# 07_POWER-RAILS.net
KiCad netlist of a schematic drawn in Altium Designer
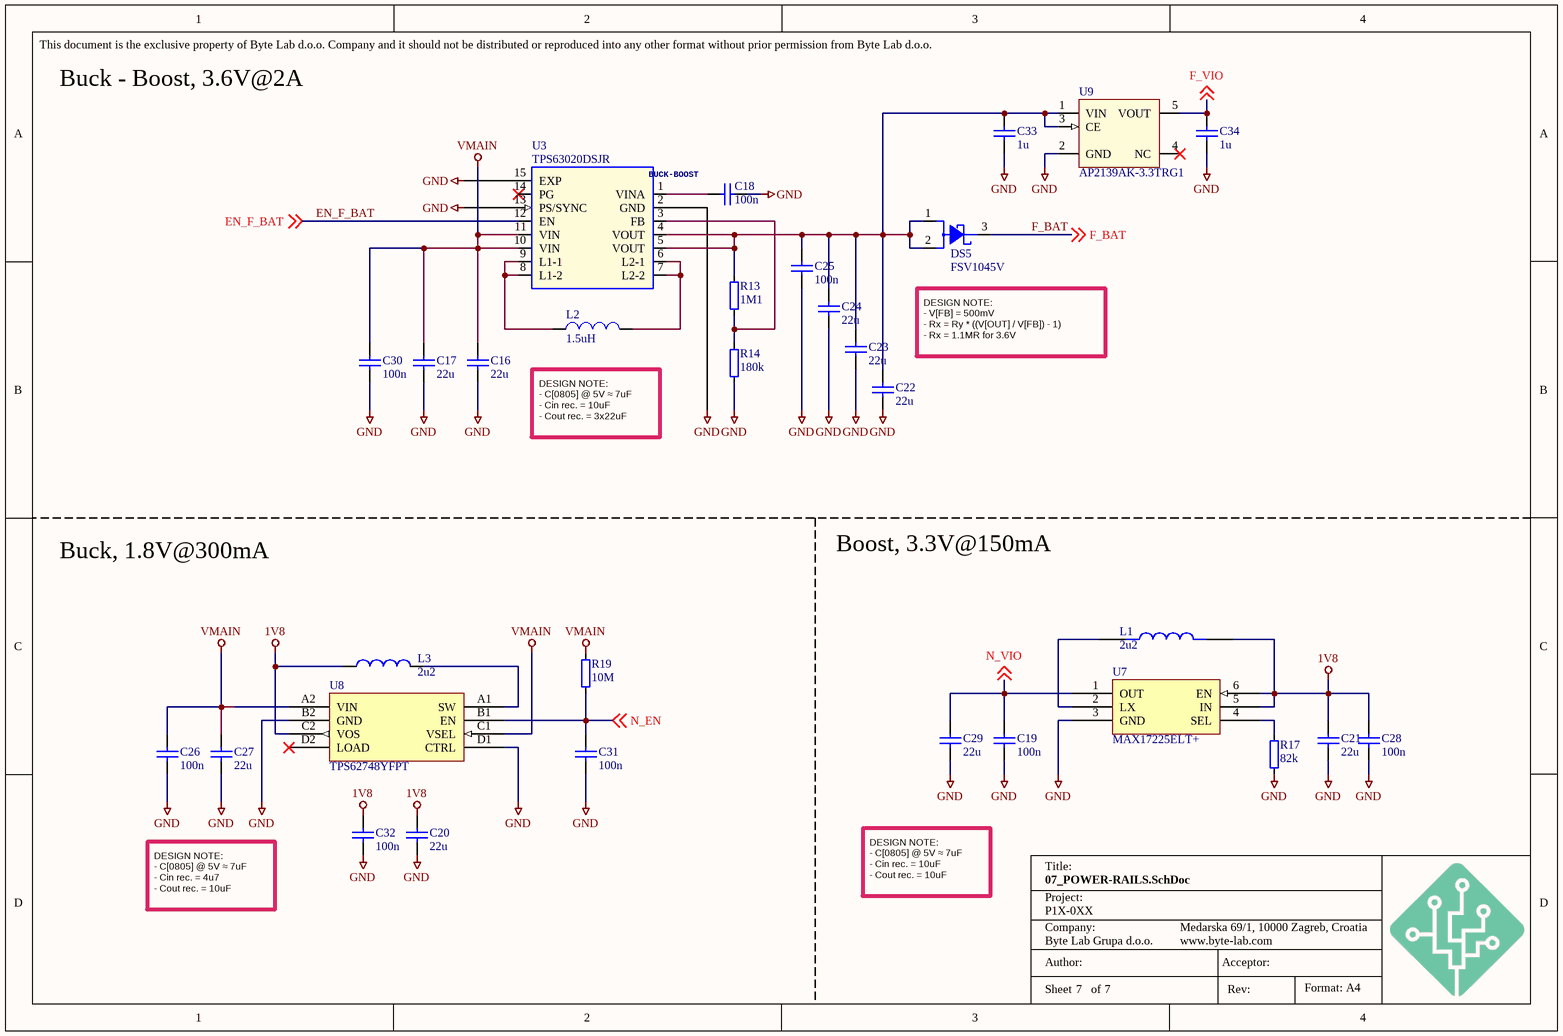
[diagram p0: 07_POWER-RAILS.SchDoc]

(export (version "E")
  (design (tool "Eeschema 10.0.6"))
  (components
    (comp (ref "C16")
      (value "22u")
      (footprint "C-0805")
      (description "Capacitor ceramic 22u ±10% X5R 16V 0805")
      (fields
        (field (name "BL PART NUMBER") "2006-222")
        (field (name "DRAWN_BY") "Fumic")
        (field (name "CHECKED_BY") "Hamin")
      )
      (libsource (lib "BL_Passive") (part "C0805-22u-16V-X5R"))
    )
    (comp (ref "C17")
      (value "22u")
      (footprint "C-0805")
      (description "Capacitor ceramic 22u ±10% X5R 16V 0805")
      (fields
        (field (name "BL PART NUMBER") "2006-222")
        (field (name "DRAWN_BY") "Fumic")
        (field (name "CHECKED_BY") "Hamin")
      )
      (libsource (lib "BL_Passive") (part "C0805-22u-16V-X5R"))
    )
    (comp (ref "C18")
      (value "100n")
      (footprint "C-0402")
      (description "Capacitor ceramic 100n ±10% X7R 16V 0402")
      (fields
        (field (name "BL PART NUMBER") "2000-908")
        (field (name "DRAWN_BY") "Puskar")
        (field (name "CHECKED_BY") "Dodig")
      )
      (libsource (lib "BL_Passive") (part "C0402-100n-16V-X7R"))
    )
    (comp (ref "C19")
      (value "100n")
      (footprint "C-0402")
      (description "Capacitor ceramic 100n ±10% X7R 16V 0402")
      (fields
        (field (name "BL PART NUMBER") "2000-908")
        (field (name "DRAWN_BY") "Puskar")
        (field (name "CHECKED_BY") "Dodig")
      )
      (libsource (lib "BL_Passive") (part "C0402-100n-16V-X7R"))
    )
    (comp (ref "C20")
      (value "22u")
      (footprint "C-0805")
      (description "Capacitor ceramic 22u ±10% X5R 16V 0805")
      (fields
        (field (name "BL PART NUMBER") "2006-222")
        (field (name "DRAWN_BY") "Fumic")
        (field (name "CHECKED_BY") "Hamin")
      )
      (libsource (lib "BL_Passive") (part "C0805-22u-16V-X5R"))
    )
    (comp (ref "C21")
      (value "22u")
      (footprint "C-0805")
      (description "Capacitor ceramic 22u ±10% X5R 16V 0805")
      (fields
        (field (name "BL PART NUMBER") "2006-222")
        (field (name "DRAWN_BY") "Fumic")
        (field (name "CHECKED_BY") "Hamin")
      )
      (libsource (lib "BL_Passive") (part "C0805-22u-16V-X5R"))
    )
    (comp (ref "C22")
      (value "22u")
      (footprint "C-0805")
      (description "Capacitor ceramic 22u ±10% X5R 16V 0805")
      (fields
        (field (name "BL PART NUMBER") "2006-222")
        (field (name "DRAWN_BY") "Fumic")
        (field (name "CHECKED_BY") "Hamin")
      )
      (libsource (lib "BL_Passive") (part "C0805-22u-16V-X5R"))
    )
    (comp (ref "C23")
      (value "22u")
      (footprint "C-0805")
      (description "Capacitor ceramic 22u ±10% X5R 16V 0805")
      (fields
        (field (name "BL PART NUMBER") "2006-222")
        (field (name "DRAWN_BY") "Fumic")
        (field (name "CHECKED_BY") "Hamin")
      )
      (libsource (lib "BL_Passive") (part "C0805-22u-16V-X5R"))
    )
    (comp (ref "C24")
      (value "22u")
      (footprint "C-0805")
      (description "Capacitor ceramic 22u ±10% X5R 16V 0805")
      (fields
        (field (name "BL PART NUMBER") "2006-222")
        (field (name "DRAWN_BY") "Fumic")
        (field (name "CHECKED_BY") "Hamin")
      )
      (libsource (lib "BL_Passive") (part "C0805-22u-16V-X5R"))
    )
    (comp (ref "C25")
      (value "100n")
      (footprint "C-0402")
      (description "Capacitor ceramic 100n ±10% X7R 16V 0402")
      (fields
        (field (name "BL PART NUMBER") "2000-908")
        (field (name "DRAWN_BY") "Puskar")
        (field (name "CHECKED_BY") "Dodig")
      )
      (libsource (lib "BL_Passive") (part "C0402-100n-16V-X7R"))
    )
    (comp (ref "C26")
      (value "100n")
      (footprint "C-0402")
      (description "Capacitor ceramic 100n ±10% X7R 16V 0402")
      (fields
        (field (name "BL PART NUMBER") "2000-908")
        (field (name "DRAWN_BY") "Puskar")
        (field (name "CHECKED_BY") "Dodig")
      )
      (libsource (lib "BL_Passive") (part "C0402-100n-16V-X7R"))
    )
    (comp (ref "C27")
      (value "22u")
      (footprint "C-0805")
      (description "Capacitor ceramic 22u ±10% X5R 16V 0805")
      (fields
        (field (name "BL PART NUMBER") "2006-222")
        (field (name "DRAWN_BY") "Fumic")
        (field (name "CHECKED_BY") "Hamin")
      )
      (libsource (lib "BL_Passive") (part "C0805-22u-16V-X5R"))
    )
    (comp (ref "C28")
      (value "100n")
      (footprint "C-0402")
      (description "Capacitor ceramic 100n ±10% X7R 16V 0402")
      (fields
        (field (name "BL PART NUMBER") "2000-908")
        (field (name "DRAWN_BY") "Puskar")
        (field (name "CHECKED_BY") "Dodig")
      )
      (libsource (lib "BL_Passive") (part "C0402-100n-16V-X7R"))
    )
    (comp (ref "C29")
      (value "22u")
      (footprint "C-0805")
      (description "Capacitor ceramic 22u ±10% X5R 16V 0805")
      (fields
        (field (name "BL PART NUMBER") "2006-222")
        (field (name "DRAWN_BY") "Fumic")
        (field (name "CHECKED_BY") "Hamin")
      )
      (libsource (lib "BL_Passive") (part "C0805-22u-16V-X5R"))
    )
    (comp (ref "C30")
      (value "100n")
      (footprint "C-0402")
      (description "Capacitor ceramic 100n ±10% X7R 16V 0402")
      (fields
        (field (name "BL PART NUMBER") "2000-908")
        (field (name "DRAWN_BY") "Puskar")
        (field (name "CHECKED_BY") "Dodig")
      )
      (libsource (lib "BL_Passive") (part "C0402-100n-16V-X7R"))
    )
    (comp (ref "C31")
      (value "100n")
      (footprint "C-0402")
      (description "Capacitor ceramic 100n ±10% X7R 16V 0402")
      (fields
        (field (name "BL PART NUMBER") "2000-908")
        (field (name "DRAWN_BY") "Puskar")
        (field (name "CHECKED_BY") "Dodig")
      )
      (libsource (lib "BL_Passive") (part "C0402-100n-16V-X7R"))
    )
    (comp (ref "C32")
      (value "100n")
      (footprint "C-0402")
      (description "Capacitor ceramic 100n ±10% X7R 16V 0402")
      (fields
        (field (name "BL PART NUMBER") "2000-908")
        (field (name "DRAWN_BY") "Puskar")
        (field (name "CHECKED_BY") "Dodig")
      )
      (libsource (lib "BL_Passive") (part "C0402-100n-16V-X7R"))
    )
    (comp (ref "C33")
      (value "1u")
      (footprint "C-0603")
      (description "Capacitor ceramic 1u ±10% X5R 25V")
      (fields
        (field (name "MANUFACTURER") "Yageo")
        (field (name "BL PART NUMBER") "2006-223")
        (field (name "DRAWN_BY") "Hamin")
        (field (name "CHECKED_BY") "Golubic")
      )
      (libsource (lib "BL_Passive") (part "C0603-1u-25V-X5R"))
    )
    (comp (ref "C34")
      (value "1u")
      (footprint "C-0603")
      (description "Capacitor ceramic 1u ±10% X5R 25V")
      (fields
        (field (name "MANUFACTURER") "Yageo")
        (field (name "BL PART NUMBER") "2006-223")
        (field (name "DRAWN_BY") "Hamin")
        (field (name "CHECKED_BY") "Golubic")
      )
      (libsource (lib "BL_Passive") (part "C0603-1u-25V-X5R"))
    )
    (comp (ref "DS5")
      (value "FSV1045V")
      (footprint "TO277-3")
      (description "DIODO SCHOTTKY 10A 45V FSV1045V TO277-3 SMT")
      (fields
        (field (name "BL PART NUMBER") "2007-712")
        (field (name "MANUFACTURER") "onsemi")
        (field (name "DRAWN_BY") "Blues Wireless")
      )
      (libsource (lib "n21-p2") (part "SCHOTTKY - FSV1045V - 10A/45V"))
    )
    (comp (ref "L1")
      (value "2u2")
      (footprint "IND_XFL4020-222MEC")
      (description "Power Inductors - SMD 2.2Uh Shld 8A 23.5mOhms AECQ2")
      (fields (field (name "BL PART NUMBER") "2007-483") (field (name "DRAWN_BY") "Blues Wireless"))
      (libsource (lib "n21-p2") (part "XFL4020-222MEC"))
    )
    (comp (ref "L2")
      (value "1.5uH")
      (footprint "VCHA042A-1R5MS6")
      (description "Fixed Ind 1.5UH 7.3A 15.4 Mohm")
      (fields
        (field (name "MANUFACTURER") "Cyntec")
        (field (name "MANUFACTURER PART NUMBER") "VCHA042A-1R5MS6")
        (field (name "DRAWN_BY") "Blues Wireless")
      )
      (libsource (lib "n21-p2") (part "VCHA042A-1R5MS6"))
    )
    (comp (ref "L3")
      (value "2u2")
      (footprint "1285AS-H-2R2M=P2-INDC2016X100N")
      (description "FIXED IND 2.2UH 1.5A 204MOHM SMD")
      (fields
        (field (name "MANUFACTURER") "Murata Electronics")
        (field (name "MANUFACTURER PART NUMBER") "1285AS-H-2R2M=P2")
        (field (name "DRAWN_BY") "Blues Wireless")
      )
      (libsource (lib "n21-p2") (part "1285AS-H-2R2M=P2"))
    )
    (comp (ref "R13")
      (value "1M1")
      (footprint "R-0402")
      (description "Resistor 1M1 ±1% 0402")
      (fields
        (field (name "BL PART NUMBER") "2000-730")
        (field (name "CHECKED_BY") "*")
        (field (name "DRAWN_BY") "Hamin")
      )
      (libsource (lib "BL_Passive") (part "R0402-1M1-1"))
    )
    (comp (ref "R14")
      (value "180k")
      (footprint "R-0402")
      (description "Resistor 180k ±1% 0402")
      (fields
        (field (name "BL PART NUMBER") "2001-422")
        (field (name "CHECKED_BY") "Hamin")
        (field (name "DRAWN_BY") "Dodig")
      )
      (libsource (lib "BL_Passive") (part "R0402-180k-1"))
    )
    (comp (ref "R17")
      (value "82k")
      (footprint "R-0402")
      (description "Resistor 82k ±1% 0402")
      (fields
        (field (name "MANUFACTURER") "Yageo")
        (field (name "MANUFACTURER PART NUMBER") "RC0402FR-0782KL")
        (field (name "CHECKED_BY") "Hamin")
        (field (name "DRAWN_BY") "Puskar")
      )
      (libsource (lib "BL_Passive") (part "R0402-82k-1"))
    )
    (comp (ref "R19")
      (value "10M")
      (footprint "BL_Passive:R-0402")
      (description "Resistor 10M ±1% 0402")
      (fields
        (field (name "BL PART NUMBER") "2002-832")
        (field (name "CHECKED_BY") "Dodig")
        (field (name "DRAWN_BY") "Zvonc")
      )
      (libsource (lib "BL_Passive") (part "R0402-10M-1"))
    )
    (comp (ref "U3")
      (value "TPS63020DSJR")
      (footprint "TI PVSON-14 DSJ")
      (description "I.C. DC/DC CONVERTER TPS63020DSJR TEXAS VSON14 SMT")
      (fields
        (field (name "BL PART NUMBER") "2002-405")
        (field (name "MANUFACTURER") "Texas Instruments")
        (field (name "DRAWN_BY") "Blues Wireless")
      )
      (libsource (lib "n21-p2") (part "BUCK-BOOST - TPS63020DSJR"))
    )
    (comp (ref "U7")
      (value "MAX17225ELT+")
      (footprint "MAX17225ELT+UDFN")
      (description "IC REG BOOST ADJ 1A NANO 6UDFN")
      (fields
        (field (name "MANUFACTURER") "Maxim")
        (field (name "BL PART NUMBER") "2007-481")
        (field (name "DRAWN_BY") "Blues Wireless")
      )
      (libsource (lib "n21-p2") (part "MAX17225ELT+"))
    )
    (comp (ref "U8")
      (value "TPS62748YFPT")
      (footprint "TPS62748YFPT-DSBGA4x2")
      (description "IC REG BUCK PROG 300MA 8DSBGA")
      (fields
        (field (name "MANUFACTURER") "Texas Instruments")
        (field (name "BL PART NUMBER") "2007-480")
        (field (name "DRAWN_BY") "Blues Wireless")
      )
      (libsource (lib "n21-p2") (part "TPS62748YFPT"))
    )
    (comp (ref "U9")
      (value "AP2139AK-3.3TRG1")
      (footprint "BL_Components:SOT-23-5(M5)")
      (description "IC REG LINEAR 3.3V 250MA SOT23-5")
      (fields
        (field (name "MANUFACTURER") "Diodes Incorporated")
        (field (name "BL PART NUMBER") "2006-845")
        (field (name "CHECKED_BY") "Hlupic")
        (field (name "DRAWN_BY") "Marsic")
      )
      (libsource (lib "BL_Analog") (part "AP2139AK-3.3TRG1"))
    )
  )
  (nets
    (net (code "1") (name "1V8") (class "Default")
      (node (ref "C20") (pin "1") (pinfunction "1_1") (pintype "passive"))
      (node (ref "C21") (pin "2") (pinfunction "2_2") (pintype "passive"))
      (node (ref "C28") (pin "2") (pinfunction "2_2") (pintype "passive"))
      (node (ref "C32") (pin "2") (pinfunction "2_2") (pintype "passive"))
      (node (ref "L1") (pin "2") (pinfunction "2_2") (pintype "passive"))
      (node (ref "L3") (pin "1") (pinfunction "1_1") (pintype "passive"))
      (node (ref "U7") (pin "5") (pinfunction "IN_5") (pintype "passive"))
      (node (ref "U7") (pin "6") (pinfunction "EN_6") (pintype "input"))
      (node (ref "U8") (pin "C2") (pinfunction "VOS_C2") (pintype "output"))
    )
    (net (code "2") (name "EN_F_BAT") (class "Default")
      (node (ref "U3") (pin "12") (pinfunction "EN_12") (pintype "passive"))
    )
    (net (code "3") (name "F_BAT") (class "Default")
      (node (ref "DS5") (pin "3") (pinfunction "C_3") (pintype "passive"))
    )
    (net (code "4") (name "F_VIO") (class "Default")
      (node (ref "C34") (pin "2") (pinfunction "2_2") (pintype "passive"))
      (node (ref "U9") (pin "5") (pinfunction "VOUT_5") (pintype "power_in"))
    )
    (net (code "5") (name "GND") (class "Default")
      (node (ref "C16") (pin "1") (pinfunction "1_1") (pintype "passive"))
      (node (ref "C17") (pin "1") (pinfunction "1_1") (pintype "passive"))
      (node (ref "C18") (pin "1") (pinfunction "1_1") (pintype "passive"))
      (node (ref "C19") (pin "1") (pinfunction "1_1") (pintype "passive"))
      (node (ref "C20") (pin "2") (pinfunction "2_2") (pintype "passive"))
      (node (ref "C21") (pin "1") (pinfunction "1_1") (pintype "passive"))
      (node (ref "C22") (pin "2") (pinfunction "2_2") (pintype "passive"))
      (node (ref "C23") (pin "2") (pinfunction "2_2") (pintype "passive"))
      (node (ref "C24") (pin "2") (pinfunction "2_2") (pintype "passive"))
      (node (ref "C25") (pin "1") (pinfunction "1_1") (pintype "passive"))
      (node (ref "C26") (pin "1") (pinfunction "1_1") (pintype "passive"))
      (node (ref "C27") (pin "1") (pinfunction "1_1") (pintype "passive"))
      (node (ref "C28") (pin "1") (pinfunction "1_1") (pintype "passive"))
      (node (ref "C29") (pin "2") (pinfunction "2_2") (pintype "passive"))
      (node (ref "C30") (pin "1") (pinfunction "1_1") (pintype "passive"))
      (node (ref "C31") (pin "1") (pinfunction "1_1") (pintype "passive"))
      (node (ref "C32") (pin "1") (pinfunction "1_1") (pintype "passive"))
      (node (ref "C33") (pin "1") (pinfunction "1_1") (pintype "passive"))
      (node (ref "C34") (pin "1") (pinfunction "1_1") (pintype "passive"))
      (node (ref "R14") (pin "1") (pintype "passive"))
      (node (ref "R17") (pin "2") (pintype "passive"))
      (node (ref "U3") (pin "13") (pinfunction "PS/SYNC_13") (pintype "input"))
      (node (ref "U3") (pin "15") (pinfunction "EXP_15") (pintype "passive"))
      (node (ref "U3") (pin "2") (pinfunction "GND_2") (pintype "power_in"))
      (node (ref "U7") (pin "3") (pinfunction "GND_3") (pintype "passive"))
      (node (ref "U8") (pin "B2") (pinfunction "GND_B2") (pintype "passive"))
      (node (ref "U8") (pin "D1") (pinfunction "CTRL_D1") (pintype "passive"))
      (node (ref "U9") (pin "2") (pinfunction "GND_2") (pintype "power_in"))
    )
    (net (code "6") (name "N_EN") (class "Default")
      (node (ref "C31") (pin "2") (pinfunction "2_2") (pintype "passive"))
      (node (ref "R19") (pin "1") (pintype "passive"))
      (node (ref "U8") (pin "B1") (pinfunction "EN_B1") (pintype "passive"))
    )
    (net (code "7") (name "N_VIO") (class "Default")
      (node (ref "C19") (pin "2") (pinfunction "2_2") (pintype "passive"))
      (node (ref "C29") (pin "1") (pinfunction "1_1") (pintype "passive"))
      (node (ref "U7") (pin "1") (pinfunction "OUT_1") (pintype "passive"))
    )
    (net (code "8") (name "Net-(DS5-A1)") (class "Default")
      (node (ref "C22") (pin "1") (pinfunction "1_1") (pintype "passive"))
      (node (ref "C23") (pin "1") (pinfunction "1_1") (pintype "passive"))
      (node (ref "C24") (pin "1") (pinfunction "1_1") (pintype "passive"))
      (node (ref "C25") (pin "2") (pinfunction "2_2") (pintype "passive"))
      (node (ref "C33") (pin "2") (pinfunction "2_2") (pintype "passive"))
      (node (ref "DS5") (pin "1") (pinfunction "A1_1") (pintype "passive"))
      (node (ref "DS5") (pin "2") (pinfunction "A2_2") (pintype "passive"))
      (node (ref "R13") (pin "2") (pintype "passive"))
      (node (ref "U3") (pin "4") (pinfunction "VOUT_4") (pintype "power_in"))
      (node (ref "U3") (pin "5") (pinfunction "VOUT_5") (pintype "power_in"))
      (node (ref "U9") (pin "1") (pinfunction "VIN_1") (pintype "power_in"))
      (node (ref "U9") (pin "3") (pinfunction "CE_3") (pintype "input"))
    )
    (net (code "9") (name "Net-(L2-A)") (class "Default")
      (node (ref "L2") (pin "2") (pinfunction "A_2") (pintype "passive"))
      (node (ref "U3") (pin "8") (pinfunction "L1-2_8") (pintype "passive"))
      (node (ref "U3") (pin "9") (pinfunction "L1-1_9") (pintype "passive"))
    )
    (net (code "10") (name "Net-(L2-C)") (class "Default")
      (node (ref "L2") (pin "1") (pinfunction "C_1") (pintype "passive"))
      (node (ref "U3") (pin "6") (pinfunction "L2-1_6") (pintype "passive"))
      (node (ref "U3") (pin "7") (pinfunction "L2-2_7") (pintype "passive"))
    )
    (net (code "11") (name "Net-(U3-FB)") (class "Default")
      (node (ref "R13") (pin "1") (pintype "passive"))
      (node (ref "R14") (pin "2") (pintype "passive"))
      (node (ref "U3") (pin "3") (pinfunction "FB_3") (pintype "passive"))
    )
    (net (code "12") (name "Net-(U3-VINA)") (class "Default")
      (node (ref "C18") (pin "2") (pinfunction "2_2") (pintype "passive"))
      (node (ref "U3") (pin "1") (pinfunction "VINA_1") (pintype "power_in"))
    )
    (net (code "13") (name "Net-(U7-LX)") (class "Default")
      (node (ref "L1") (pin "1") (pinfunction "1_1") (pintype "passive"))
      (node (ref "U7") (pin "2") (pinfunction "LX_2") (pintype "passive"))
    )
    (net (code "14") (name "Net-(U7-SEL)") (class "Default")
      (node (ref "R17") (pin "1") (pintype "passive"))
      (node (ref "U7") (pin "4") (pinfunction "SEL_4") (pintype "passive"))
    )
    (net (code "15") (name "Net-(U8-SW)") (class "Default")
      (node (ref "L3") (pin "2") (pinfunction "2_2") (pintype "passive"))
      (node (ref "U8") (pin "A1") (pinfunction "SW_A1") (pintype "passive"))
    )
    (net (code "16") (name "VMAIN") (class "Default")
      (node (ref "C16") (pin "2") (pinfunction "2_2") (pintype "passive"))
      (node (ref "C17") (pin "2") (pinfunction "2_2") (pintype "passive"))
      (node (ref "C26") (pin "2") (pinfunction "2_2") (pintype "passive"))
      (node (ref "C27") (pin "2") (pinfunction "2_2") (pintype "passive"))
      (node (ref "C30") (pin "2") (pinfunction "2_2") (pintype "passive"))
      (node (ref "R19") (pin "2") (pintype "passive"))
      (node (ref "U3") (pin "10") (pinfunction "VIN_10") (pintype "power_in"))
      (node (ref "U3") (pin "11") (pinfunction "VIN_11") (pintype "power_in"))
      (node (ref "U8") (pin "A2") (pinfunction "VIN_A2") (pintype "passive"))
      (node (ref "U8") (pin "C1") (pinfunction "VSEL_C1") (pintype "input"))
    )
    (net (code "17") (name "unconnected-(U3-PG-Pad14)") (class "Default")
      (node (ref "U3") (pin "14") (pinfunction "PG_14") (pintype "open_collector+no_connect"))
    )
    (net (code "18") (name "unconnected-(U8-LOAD-PadD2)") (class "Default")
      (node (ref "U8") (pin "D2") (pinfunction "LOAD_D2") (pintype "passive+no_connect"))
    )
    (net (code "19") (name "unconnected-(U9-NC-Pad4)") (class "Default")
      (node (ref "U9") (pin "4") (pinfunction "NC_4") (pintype "passive+no_connect"))
    )
  )
)
